# eib-128.net
KiCad netlist of a schematic drawn in EAGLE
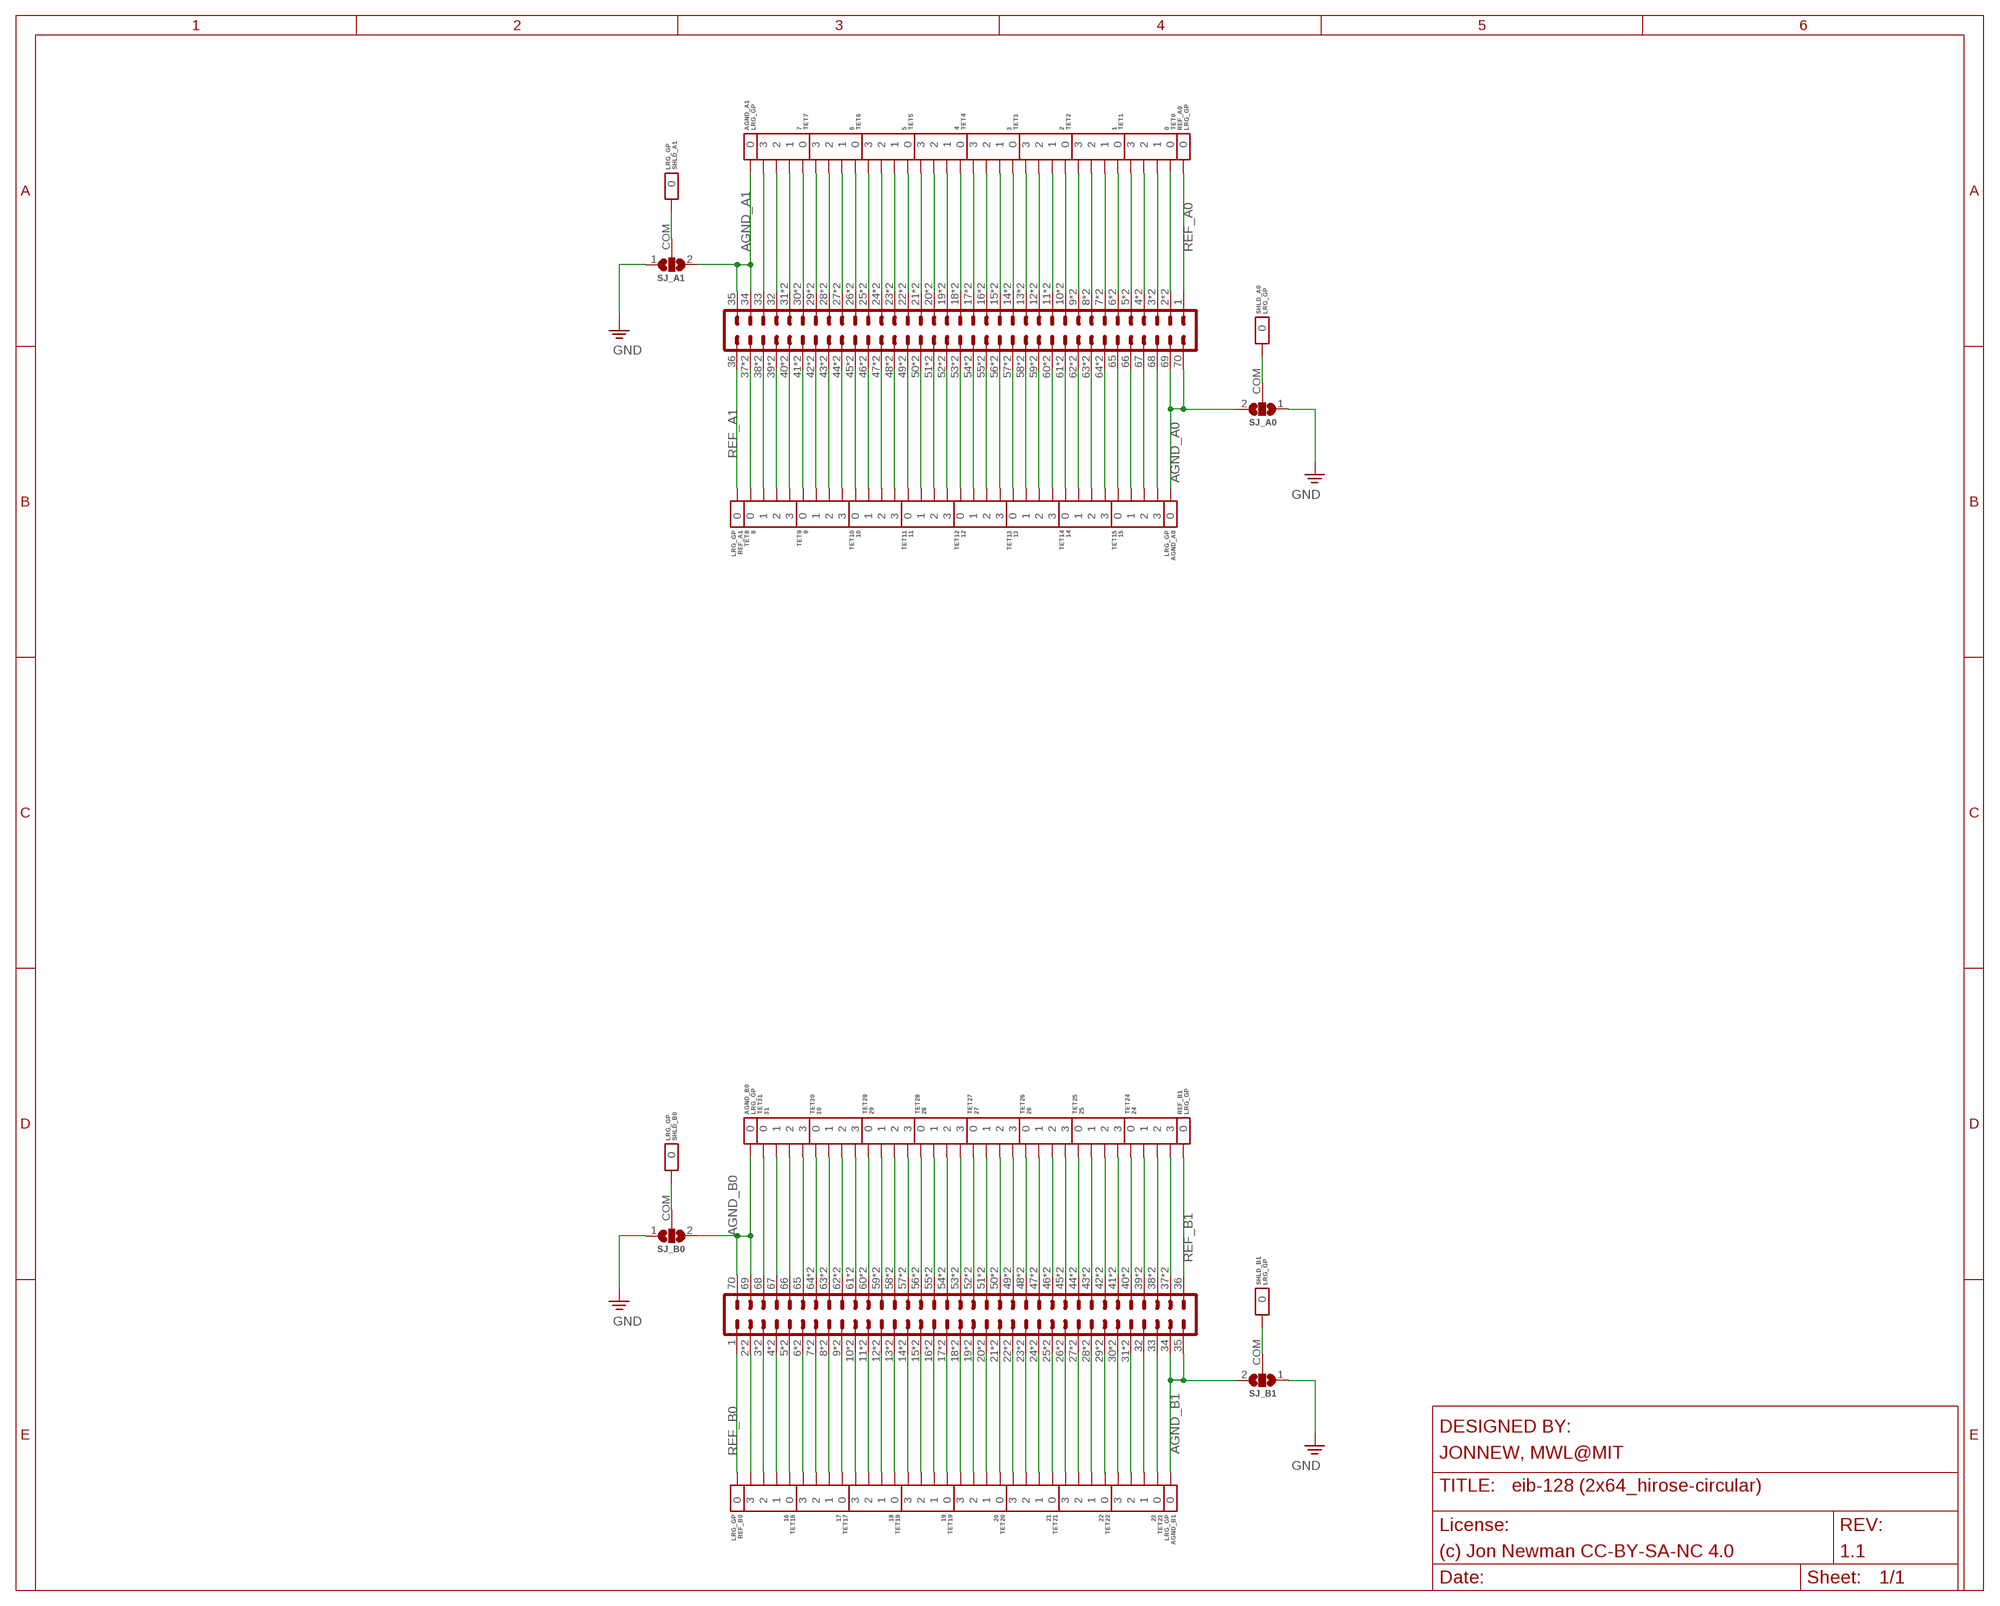
[diagram p0: schematic, sheet 1]

(export (version "E")
  (design (tool "Eeschema 10.0.6"))
  (components
    (comp (ref "AGND_A0")
      (value "LRG_GP")
      (footprint "eagle-import:GOLDPIN_0.5ID_0.7OD")
      (libsource (lib "eagle-import") (part "GOLDPIN_0.5ID_0.7OD"))
    )
    (comp (ref "AGND_A1")
      (value "LRG_GP")
      (footprint "eagle-import:GOLDPIN_0.5ID_0.7OD")
      (libsource (lib "eagle-import") (part "GOLDPIN_0.5ID_0.7OD"))
    )
    (comp (ref "AGND_B0")
      (value "LRG_GP")
      (footprint "eagle-import:GOLDPIN_0.5ID_0.7OD")
      (libsource (lib "eagle-import") (part "GOLDPIN_0.5ID_0.7OD"))
    )
    (comp (ref "AGND_B1")
      (value "LRG_GP")
      (footprint "eagle-import:GOLDPIN_0.5ID_0.7OD")
      (libsource (lib "eagle-import") (part "GOLDPIN_0.5ID_0.7OD"))
    )
    (comp (ref "AIN_N0T")
      (value "DF40HEAD")
      (footprint "eagle-import:DF40-70HEAD-EIB")
      (libsource (lib "eagle-import") (part "PINHD-2X35_DF40HEAD-EIB"))
    )
    (comp (ref "AIN_S0T")
      (value "DF40HEAD")
      (footprint "eagle-import:DF40-70HEAD-EIB")
      (libsource (lib "eagle-import") (part "PINHD-2X35_DF40HEAD-EIB"))
    )
    (comp (ref "REF_A0")
      (value "LRG_GP")
      (footprint "eagle-import:GOLDPIN_0.5ID_0.7OD")
      (libsource (lib "eagle-import") (part "GOLDPIN_0.5ID_0.7OD"))
    )
    (comp (ref "REF_A1")
      (value "LRG_GP")
      (footprint "eagle-import:GOLDPIN_0.5ID_0.7OD")
      (libsource (lib "eagle-import") (part "GOLDPIN_0.5ID_0.7OD"))
    )
    (comp (ref "REF_B0")
      (value "LRG_GP")
      (footprint "eagle-import:GOLDPIN_0.5ID_0.7OD")
      (libsource (lib "eagle-import") (part "GOLDPIN_0.5ID_0.7OD"))
    )
    (comp (ref "REF_B1")
      (value "LRG_GP")
      (footprint "eagle-import:GOLDPIN_0.5ID_0.7OD")
      (libsource (lib "eagle-import") (part "GOLDPIN_0.5ID_0.7OD"))
    )
    (comp (ref "SHLD_A0")
      (value "LRG_GP")
      (footprint "eagle-import:GOLDPIN_0.5ID_0.7OD")
      (libsource (lib "eagle-import") (part "GOLDPIN_0.5ID_0.7OD"))
    )
    (comp (ref "SHLD_A1")
      (value "LRG_GP")
      (footprint "eagle-import:GOLDPIN_0.5ID_0.7OD")
      (libsource (lib "eagle-import") (part "GOLDPIN_0.5ID_0.7OD"))
    )
    (comp (ref "SHLD_B0")
      (value "LRG_GP")
      (footprint "eagle-import:GOLDPIN_0.5ID_0.7OD")
      (libsource (lib "eagle-import") (part "GOLDPIN_0.5ID_0.7OD"))
    )
    (comp (ref "SHLD_B1")
      (value "LRG_GP")
      (footprint "eagle-import:GOLDPIN_0.5ID_0.7OD")
      (libsource (lib "eagle-import") (part "GOLDPIN_0.5ID_0.7OD"))
    )
    (comp (ref "SJ_A0")
      (value "SJ2_0402")
      (footprint "eagle-import:SJ_2_0402")
      (libsource (lib "eagle-import") (part "SJ2_0402"))
    )
    (comp (ref "SJ_A1")
      (value "SJ2_0402")
      (footprint "eagle-import:SJ_2_0402")
      (libsource (lib "eagle-import") (part "SJ2_0402"))
    )
    (comp (ref "SJ_B0")
      (value "SJ2_0402")
      (footprint "eagle-import:SJ_2_0402")
      (libsource (lib "eagle-import") (part "SJ2_0402"))
    )
    (comp (ref "SJ_B1")
      (value "SJ2_0402")
      (footprint "eagle-import:SJ_2_0402")
      (libsource (lib "eagle-import") (part "SJ2_0402"))
    )
    (comp (ref "TET0")
      (value "0")
      (footprint "eagle-import:TETRODE_128_0.5ID_0.7OD")
      (libsource (lib "eagle-import") (part "TETRODE_128_0.5ID_0.7OD"))
    )
    (comp (ref "TET1")
      (value "1")
      (footprint "eagle-import:TETRODE_128_0.5ID_0.7OD")
      (libsource (lib "eagle-import") (part "TETRODE_128_0.5ID_0.7OD"))
    )
    (comp (ref "TET2")
      (value "2")
      (footprint "eagle-import:TETRODE_128_0.5ID_0.7OD")
      (libsource (lib "eagle-import") (part "TETRODE_128_0.5ID_0.7OD"))
    )
    (comp (ref "TET3")
      (value "3")
      (footprint "eagle-import:TETRODE_128_0.5ID_0.7OD")
      (libsource (lib "eagle-import") (part "TETRODE_128_0.5ID_0.7OD"))
    )
    (comp (ref "TET4")
      (value "4")
      (footprint "eagle-import:TETRODE_128_0.5ID_0.7OD")
      (libsource (lib "eagle-import") (part "TETRODE_128_0.5ID_0.7OD"))
    )
    (comp (ref "TET5")
      (value "5")
      (footprint "eagle-import:TETRODE_128_0.5ID_0.7OD")
      (libsource (lib "eagle-import") (part "TETRODE_128_0.5ID_0.7OD"))
    )
    (comp (ref "TET6")
      (value "6")
      (footprint "eagle-import:TETRODE_128_0.5ID_0.7OD")
      (libsource (lib "eagle-import") (part "TETRODE_128_0.5ID_0.7OD"))
    )
    (comp (ref "TET7")
      (value "7")
      (footprint "eagle-import:TETRODE_128_0.5ID_0.7OD")
      (libsource (lib "eagle-import") (part "TETRODE_128_0.5ID_0.7OD"))
    )
    (comp (ref "TET8")
      (value "8")
      (footprint "eagle-import:TETRODE_128_0.5ID_0.7OD")
      (libsource (lib "eagle-import") (part "TETRODE_128_0.5ID_0.7OD"))
    )
    (comp (ref "TET9")
      (value "9")
      (footprint "eagle-import:TETRODE_128_0.5ID_0.7OD")
      (libsource (lib "eagle-import") (part "TETRODE_128_0.5ID_0.7OD"))
    )
    (comp (ref "TET10")
      (value "10")
      (footprint "eagle-import:TETRODE_128_0.5ID_0.7OD")
      (libsource (lib "eagle-import") (part "TETRODE_128_0.5ID_0.7OD"))
    )
    (comp (ref "TET11")
      (value "11")
      (footprint "eagle-import:TETRODE_128_0.5ID_0.7OD")
      (libsource (lib "eagle-import") (part "TETRODE_128_0.5ID_0.7OD"))
    )
    (comp (ref "TET12")
      (value "12")
      (footprint "eagle-import:TETRODE_128_0.5ID_0.7OD")
      (libsource (lib "eagle-import") (part "TETRODE_128_0.5ID_0.7OD"))
    )
    (comp (ref "TET13")
      (value "13")
      (footprint "eagle-import:TETRODE_128_0.5ID_0.7OD")
      (libsource (lib "eagle-import") (part "TETRODE_128_0.5ID_0.7OD"))
    )
    (comp (ref "TET14")
      (value "14")
      (footprint "eagle-import:TETRODE_128_0.5ID_0.7OD")
      (libsource (lib "eagle-import") (part "TETRODE_128_0.5ID_0.7OD"))
    )
    (comp (ref "TET15")
      (value "15")
      (footprint "eagle-import:TETRODE_128_0.5ID_0.7OD")
      (libsource (lib "eagle-import") (part "TETRODE_128_0.5ID_0.7OD"))
    )
    (comp (ref "TET16")
      (value "16")
      (footprint "eagle-import:TETRODE_128_0.5ID_0.7OD")
      (libsource (lib "eagle-import") (part "TETRODE_128_0.5ID_0.7OD"))
    )
    (comp (ref "TET17")
      (value "17")
      (footprint "eagle-import:TETRODE_128_0.5ID_0.7OD")
      (libsource (lib "eagle-import") (part "TETRODE_128_0.5ID_0.7OD"))
    )
    (comp (ref "TET18")
      (value "18")
      (footprint "eagle-import:TETRODE_128_0.5ID_0.7OD")
      (libsource (lib "eagle-import") (part "TETRODE_128_0.5ID_0.7OD"))
    )
    (comp (ref "TET19")
      (value "19")
      (footprint "eagle-import:TETRODE_128_0.5ID_0.7OD")
      (libsource (lib "eagle-import") (part "TETRODE_128_0.5ID_0.7OD"))
    )
    (comp (ref "TET20")
      (value "20")
      (footprint "eagle-import:TETRODE_128_0.5ID_0.7OD")
      (libsource (lib "eagle-import") (part "TETRODE_128_0.5ID_0.7OD"))
    )
    (comp (ref "TET21")
      (value "21")
      (footprint "eagle-import:TETRODE_128_0.5ID_0.7OD")
      (libsource (lib "eagle-import") (part "TETRODE_128_0.5ID_0.7OD"))
    )
    (comp (ref "TET22")
      (value "22")
      (footprint "eagle-import:TETRODE_128_0.5ID_0.7OD")
      (libsource (lib "eagle-import") (part "TETRODE_128_0.5ID_0.7OD"))
    )
    (comp (ref "TET23")
      (value "23")
      (footprint "eagle-import:TETRODE_128_0.5ID_0.7OD")
      (libsource (lib "eagle-import") (part "TETRODE_128_0.5ID_0.7OD"))
    )
    (comp (ref "TET24")
      (value "24")
      (footprint "eagle-import:TETRODE_128_0.5ID_0.7OD")
      (libsource (lib "eagle-import") (part "TETRODE_128_0.5ID_0.7OD"))
    )
    (comp (ref "TET25")
      (value "25")
      (footprint "eagle-import:TETRODE_128_0.5ID_0.7OD")
      (libsource (lib "eagle-import") (part "TETRODE_128_0.5ID_0.7OD"))
    )
    (comp (ref "TET26")
      (value "26")
      (footprint "eagle-import:TETRODE_128_0.5ID_0.7OD")
      (libsource (lib "eagle-import") (part "TETRODE_128_0.5ID_0.7OD"))
    )
    (comp (ref "TET27")
      (value "27")
      (footprint "eagle-import:TETRODE_128_0.5ID_0.7OD")
      (libsource (lib "eagle-import") (part "TETRODE_128_0.5ID_0.7OD"))
    )
    (comp (ref "TET28")
      (value "28")
      (footprint "eagle-import:TETRODE_128_0.5ID_0.7OD")
      (libsource (lib "eagle-import") (part "TETRODE_128_0.5ID_0.7OD"))
    )
    (comp (ref "TET29")
      (value "29")
      (footprint "eagle-import:TETRODE_128_0.5ID_0.7OD")
      (libsource (lib "eagle-import") (part "TETRODE_128_0.5ID_0.7OD"))
    )
    (comp (ref "TET30")
      (value "30")
      (footprint "eagle-import:TETRODE_128_0.5ID_0.7OD")
      (libsource (lib "eagle-import") (part "TETRODE_128_0.5ID_0.7OD"))
    )
    (comp (ref "TET31")
      (value "31")
      (footprint "eagle-import:TETRODE_128_0.5ID_0.7OD")
      (libsource (lib "eagle-import") (part "TETRODE_128_0.5ID_0.7OD"))
    )
  )
  (nets
    (net (code "1") (name "/AGND_A0") (class "Default")
      (node (ref "AGND_A0") (pin "P$1") (pinfunction "0_P$1") (pintype "bidirectional"))
      (node (ref "AIN_N0T") (pin "69") (pinfunction "69_69") (pintype "bidirectional"))
      (node (ref "AIN_N0T") (pin "70") (pinfunction "70_70") (pintype "bidirectional"))
      (node (ref "SJ_A0") (pin "2") (pinfunction "2_2") (pintype "passive"))
    )
    (net (code "2") (name "/AGND_A1") (class "Default")
      (node (ref "AGND_A1") (pin "P$1") (pinfunction "0_P$1") (pintype "bidirectional"))
      (node (ref "AIN_N0T") (pin "34") (pinfunction "34_34") (pintype "bidirectional"))
      (node (ref "AIN_N0T") (pin "35") (pinfunction "35_35") (pintype "bidirectional"))
      (node (ref "SJ_A1") (pin "2") (pinfunction "2_2") (pintype "passive"))
    )
    (net (code "3") (name "/AGND_B0") (class "Default")
      (node (ref "AGND_B0") (pin "P$1") (pinfunction "0_P$1") (pintype "bidirectional"))
      (node (ref "AIN_S0T") (pin "69") (pinfunction "69_69") (pintype "bidirectional"))
      (node (ref "AIN_S0T") (pin "70") (pinfunction "70_70") (pintype "bidirectional"))
      (node (ref "SJ_B0") (pin "2") (pinfunction "2_2") (pintype "passive"))
    )
    (net (code "4") (name "/AGND_B1") (class "Default")
      (node (ref "AGND_B1") (pin "P$1") (pinfunction "0_P$1") (pintype "bidirectional"))
      (node (ref "AIN_S0T") (pin "34") (pinfunction "34_34") (pintype "bidirectional"))
      (node (ref "AIN_S0T") (pin "35") (pinfunction "35_35") (pintype "bidirectional"))
      (node (ref "SJ_B1") (pin "2") (pinfunction "2_2") (pintype "passive"))
    )
    (net (code "5") (name "/REF_A0") (class "Default")
      (node (ref "AIN_N0T") (pin "1") (pinfunction "1_1") (pintype "bidirectional"))
      (node (ref "REF_A0") (pin "P$1") (pinfunction "0_P$1") (pintype "bidirectional"))
    )
    (net (code "6") (name "/REF_A1") (class "Default")
      (node (ref "AIN_N0T") (pin "36") (pinfunction "36_36") (pintype "bidirectional"))
      (node (ref "REF_A1") (pin "P$1") (pinfunction "0_P$1") (pintype "bidirectional"))
    )
    (net (code "7") (name "/REF_B0") (class "Default")
      (node (ref "AIN_S0T") (pin "1") (pinfunction "1_1") (pintype "bidirectional"))
      (node (ref "REF_B0") (pin "P$1") (pinfunction "0_P$1") (pintype "bidirectional"))
    )
    (net (code "8") (name "/REF_B1") (class "Default")
      (node (ref "AIN_S0T") (pin "36") (pinfunction "36_36") (pintype "bidirectional"))
      (node (ref "REF_B1") (pin "P$1") (pinfunction "0_P$1") (pintype "bidirectional"))
    )
    (net (code "9") (name "GND") (class "Default")
      (node (ref "SJ_A0") (pin "1") (pinfunction "1_1") (pintype "passive"))
      (node (ref "SJ_A1") (pin "1") (pinfunction "1_1") (pintype "passive"))
      (node (ref "SJ_B0") (pin "1") (pinfunction "1_1") (pintype "passive"))
      (node (ref "SJ_B1") (pin "1") (pinfunction "1_1") (pintype "passive"))
    )
    (net (code "10") (name "Net-(AIN_N0T-2-PadP2)") (class "Default")
      (node (ref "AIN_N0T") (pin "2") (pinfunction "2_2") (pintype "bidirectional"))
      (node (ref "AIN_N0T") (pin "P2") (pinfunction "2_P2") (pintype "bidirectional"))
      (node (ref "TET0") (pin "0") (pinfunction "0_0") (pintype "bidirectional"))
    )
    (net (code "11") (name "Net-(AIN_N0T-3-PadP3)") (class "Default")
      (node (ref "AIN_N0T") (pin "3") (pinfunction "3_3") (pintype "bidirectional"))
      (node (ref "AIN_N0T") (pin "P3") (pinfunction "3_P3") (pintype "bidirectional"))
      (node (ref "TET0") (pin "1") (pinfunction "1_1") (pintype "bidirectional"))
    )
    (net (code "12") (name "Net-(AIN_N0T-4-PadP4)") (class "Default")
      (node (ref "AIN_N0T") (pin "4") (pinfunction "4_4") (pintype "bidirectional"))
      (node (ref "AIN_N0T") (pin "P4") (pinfunction "4_P4") (pintype "bidirectional"))
      (node (ref "TET0") (pin "2") (pinfunction "2_2") (pintype "bidirectional"))
    )
    (net (code "13") (name "Net-(AIN_N0T-5-PadP5)") (class "Default")
      (node (ref "AIN_N0T") (pin "5") (pinfunction "5_5") (pintype "bidirectional"))
      (node (ref "AIN_N0T") (pin "P5") (pinfunction "5_P5") (pintype "bidirectional"))
      (node (ref "TET0") (pin "3") (pinfunction "3_3") (pintype "bidirectional"))
    )
    (net (code "14") (name "Net-(AIN_N0T-6-PadP6)") (class "Default")
      (node (ref "AIN_N0T") (pin "6") (pinfunction "6_6") (pintype "bidirectional"))
      (node (ref "AIN_N0T") (pin "P6") (pinfunction "6_P6") (pintype "bidirectional"))
      (node (ref "TET1") (pin "0") (pinfunction "0_0") (pintype "bidirectional"))
    )
    (net (code "15") (name "Net-(AIN_N0T-7-PadP7)") (class "Default")
      (node (ref "AIN_N0T") (pin "7") (pinfunction "7_7") (pintype "bidirectional"))
      (node (ref "AIN_N0T") (pin "P7") (pinfunction "7_P7") (pintype "bidirectional"))
      (node (ref "TET1") (pin "1") (pinfunction "1_1") (pintype "bidirectional"))
    )
    (net (code "16") (name "Net-(AIN_N0T-8-PadP8)") (class "Default")
      (node (ref "AIN_N0T") (pin "8") (pinfunction "8_8") (pintype "bidirectional"))
      (node (ref "AIN_N0T") (pin "P8") (pinfunction "8_P8") (pintype "bidirectional"))
      (node (ref "TET1") (pin "2") (pinfunction "2_2") (pintype "bidirectional"))
    )
    (net (code "17") (name "Net-(AIN_N0T-9-PadP9)") (class "Default")
      (node (ref "AIN_N0T") (pin "9") (pinfunction "9_9") (pintype "bidirectional"))
      (node (ref "AIN_N0T") (pin "P9") (pinfunction "9_P9") (pintype "bidirectional"))
      (node (ref "TET1") (pin "3") (pinfunction "3_3") (pintype "bidirectional"))
    )
    (net (code "18") (name "Net-(AIN_N0T-10-PadP10)") (class "Default")
      (node (ref "AIN_N0T") (pin "10") (pinfunction "10_10") (pintype "bidirectional"))
      (node (ref "AIN_N0T") (pin "P10") (pinfunction "10_P10") (pintype "bidirectional"))
      (node (ref "TET2") (pin "0") (pinfunction "0_0") (pintype "bidirectional"))
    )
    (net (code "19") (name "Net-(AIN_N0T-11-PadP11)") (class "Default")
      (node (ref "AIN_N0T") (pin "11") (pinfunction "11_11") (pintype "bidirectional"))
      (node (ref "AIN_N0T") (pin "P11") (pinfunction "11_P11") (pintype "bidirectional"))
      (node (ref "TET2") (pin "1") (pinfunction "1_1") (pintype "bidirectional"))
    )
    (net (code "20") (name "Net-(AIN_N0T-12-PadP12)") (class "Default")
      (node (ref "AIN_N0T") (pin "12") (pinfunction "12_12") (pintype "bidirectional"))
      (node (ref "AIN_N0T") (pin "P12") (pinfunction "12_P12") (pintype "bidirectional"))
      (node (ref "TET2") (pin "2") (pinfunction "2_2") (pintype "bidirectional"))
    )
    (net (code "21") (name "Net-(AIN_N0T-13-PadP13)") (class "Default")
      (node (ref "AIN_N0T") (pin "13") (pinfunction "13_13") (pintype "bidirectional"))
      (node (ref "AIN_N0T") (pin "P13") (pinfunction "13_P13") (pintype "bidirectional"))
      (node (ref "TET2") (pin "3") (pinfunction "3_3") (pintype "bidirectional"))
    )
    (net (code "22") (name "Net-(AIN_N0T-14-PadP14)") (class "Default")
      (node (ref "AIN_N0T") (pin "14") (pinfunction "14_14") (pintype "bidirectional"))
      (node (ref "AIN_N0T") (pin "P14") (pinfunction "14_P14") (pintype "bidirectional"))
      (node (ref "TET3") (pin "0") (pinfunction "0_0") (pintype "bidirectional"))
    )
    (net (code "23") (name "Net-(AIN_N0T-15-PadP15)") (class "Default")
      (node (ref "AIN_N0T") (pin "15") (pinfunction "15_15") (pintype "bidirectional"))
      (node (ref "AIN_N0T") (pin "P15") (pinfunction "15_P15") (pintype "bidirectional"))
      (node (ref "TET3") (pin "1") (pinfunction "1_1") (pintype "bidirectional"))
    )
    (net (code "24") (name "Net-(AIN_N0T-16-PadP16)") (class "Default")
      (node (ref "AIN_N0T") (pin "16") (pinfunction "16_16") (pintype "bidirectional"))
      (node (ref "AIN_N0T") (pin "P16") (pinfunction "16_P16") (pintype "bidirectional"))
      (node (ref "TET3") (pin "2") (pinfunction "2_2") (pintype "bidirectional"))
    )
    (net (code "25") (name "Net-(AIN_N0T-17-PadP17)") (class "Default")
      (node (ref "AIN_N0T") (pin "17") (pinfunction "17_17") (pintype "bidirectional"))
      (node (ref "AIN_N0T") (pin "P17") (pinfunction "17_P17") (pintype "bidirectional"))
      (node (ref "TET3") (pin "3") (pinfunction "3_3") (pintype "bidirectional"))
    )
    (net (code "26") (name "Net-(AIN_N0T-18-PadP18)") (class "Default")
      (node (ref "AIN_N0T") (pin "18") (pinfunction "18_18") (pintype "bidirectional"))
      (node (ref "AIN_N0T") (pin "P18") (pinfunction "18_P18") (pintype "bidirectional"))
      (node (ref "TET4") (pin "0") (pinfunction "0_0") (pintype "bidirectional"))
    )
    (net (code "27") (name "Net-(AIN_N0T-19-PadP19)") (class "Default")
      (node (ref "AIN_N0T") (pin "19") (pinfunction "19_19") (pintype "bidirectional"))
      (node (ref "AIN_N0T") (pin "P19") (pinfunction "19_P19") (pintype "bidirectional"))
      (node (ref "TET4") (pin "1") (pinfunction "1_1") (pintype "bidirectional"))
    )
    (net (code "28") (name "Net-(AIN_N0T-20-PadP20)") (class "Default")
      (node (ref "AIN_N0T") (pin "20") (pinfunction "20_20") (pintype "bidirectional"))
      (node (ref "AIN_N0T") (pin "P20") (pinfunction "20_P20") (pintype "bidirectional"))
      (node (ref "TET4") (pin "2") (pinfunction "2_2") (pintype "bidirectional"))
    )
    (net (code "29") (name "Net-(AIN_N0T-21-PadP21)") (class "Default")
      (node (ref "AIN_N0T") (pin "21") (pinfunction "21_21") (pintype "bidirectional"))
      (node (ref "AIN_N0T") (pin "P21") (pinfunction "21_P21") (pintype "bidirectional"))
      (node (ref "TET4") (pin "3") (pinfunction "3_3") (pintype "bidirectional"))
    )
    (net (code "30") (name "Net-(AIN_N0T-22-PadP22)") (class "Default")
      (node (ref "AIN_N0T") (pin "22") (pinfunction "22_22") (pintype "bidirectional"))
      (node (ref "AIN_N0T") (pin "P22") (pinfunction "22_P22") (pintype "bidirectional"))
      (node (ref "TET5") (pin "0") (pinfunction "0_0") (pintype "bidirectional"))
    )
    (net (code "31") (name "Net-(AIN_N0T-23-PadP23)") (class "Default")
      (node (ref "AIN_N0T") (pin "23") (pinfunction "23_23") (pintype "bidirectional"))
      (node (ref "AIN_N0T") (pin "P23") (pinfunction "23_P23") (pintype "bidirectional"))
      (node (ref "TET5") (pin "1") (pinfunction "1_1") (pintype "bidirectional"))
    )
    (net (code "32") (name "Net-(AIN_N0T-24-PadP24)") (class "Default")
      (node (ref "AIN_N0T") (pin "24") (pinfunction "24_24") (pintype "bidirectional"))
      (node (ref "AIN_N0T") (pin "P24") (pinfunction "24_P24") (pintype "bidirectional"))
      (node (ref "TET5") (pin "2") (pinfunction "2_2") (pintype "bidirectional"))
    )
    (net (code "33") (name "Net-(AIN_N0T-25-PadP25)") (class "Default")
      (node (ref "AIN_N0T") (pin "25") (pinfunction "25_25") (pintype "bidirectional"))
      (node (ref "AIN_N0T") (pin "P25") (pinfunction "25_P25") (pintype "bidirectional"))
      (node (ref "TET5") (pin "3") (pinfunction "3_3") (pintype "bidirectional"))
    )
    (net (code "34") (name "Net-(AIN_N0T-26-PadP26)") (class "Default")
      (node (ref "AIN_N0T") (pin "26") (pinfunction "26_26") (pintype "bidirectional"))
      (node (ref "AIN_N0T") (pin "P26") (pinfunction "26_P26") (pintype "bidirectional"))
      (node (ref "TET6") (pin "0") (pinfunction "0_0") (pintype "bidirectional"))
    )
    (net (code "35") (name "Net-(AIN_N0T-27-PadP27)") (class "Default")
      (node (ref "AIN_N0T") (pin "27") (pinfunction "27_27") (pintype "bidirectional"))
      (node (ref "AIN_N0T") (pin "P27") (pinfunction "27_P27") (pintype "bidirectional"))
      (node (ref "TET6") (pin "1") (pinfunction "1_1") (pintype "bidirectional"))
    )
    (net (code "36") (name "Net-(AIN_N0T-28-PadP28)") (class "Default")
      (node (ref "AIN_N0T") (pin "28") (pinfunction "28_28") (pintype "bidirectional"))
      (node (ref "AIN_N0T") (pin "P28") (pinfunction "28_P28") (pintype "bidirectional"))
      (node (ref "TET6") (pin "2") (pinfunction "2_2") (pintype "bidirectional"))
    )
    (net (code "37") (name "Net-(AIN_N0T-29-PadP29)") (class "Default")
      (node (ref "AIN_N0T") (pin "29") (pinfunction "29_29") (pintype "bidirectional"))
      (node (ref "AIN_N0T") (pin "P29") (pinfunction "29_P29") (pintype "bidirectional"))
      (node (ref "TET6") (pin "3") (pinfunction "3_3") (pintype "bidirectional"))
    )
    (net (code "38") (name "Net-(AIN_N0T-30-PadP30)") (class "Default")
      (node (ref "AIN_N0T") (pin "30") (pinfunction "30_30") (pintype "bidirectional"))
      (node (ref "AIN_N0T") (pin "P30") (pinfunction "30_P30") (pintype "bidirectional"))
      (node (ref "TET7") (pin "0") (pinfunction "0_0") (pintype "bidirectional"))
    )
    (net (code "39") (name "Net-(AIN_N0T-31-PadP31)") (class "Default")
      (node (ref "AIN_N0T") (pin "31") (pinfunction "31_31") (pintype "bidirectional"))
      (node (ref "AIN_N0T") (pin "P31") (pinfunction "31_P31") (pintype "bidirectional"))
      (node (ref "TET7") (pin "1") (pinfunction "1_1") (pintype "bidirectional"))
    )
    (net (code "40") (name "Net-(AIN_N0T-37-PadP37)") (class "Default")
      (node (ref "AIN_N0T") (pin "37") (pinfunction "37_37") (pintype "bidirectional"))
      (node (ref "AIN_N0T") (pin "P37") (pinfunction "37_P37") (pintype "bidirectional"))
      (node (ref "TET8") (pin "0") (pinfunction "0_0") (pintype "bidirectional"))
    )
    (net (code "41") (name "Net-(AIN_N0T-38-PadP38)") (class "Default")
      (node (ref "AIN_N0T") (pin "38") (pinfunction "38_38") (pintype "bidirectional"))
      (node (ref "AIN_N0T") (pin "P38") (pinfunction "38_P38") (pintype "bidirectional"))
      (node (ref "TET8") (pin "1") (pinfunction "1_1") (pintype "bidirectional"))
    )
    (net (code "42") (name "Net-(AIN_N0T-39-PadP39)") (class "Default")
      (node (ref "AIN_N0T") (pin "39") (pinfunction "39_39") (pintype "bidirectional"))
      (node (ref "AIN_N0T") (pin "P39") (pinfunction "39_P39") (pintype "bidirectional"))
      (node (ref "TET8") (pin "2") (pinfunction "2_2") (pintype "bidirectional"))
    )
    (net (code "43") (name "Net-(AIN_N0T-40-PadP40)") (class "Default")
      (node (ref "AIN_N0T") (pin "40") (pinfunction "40_40") (pintype "bidirectional"))
      (node (ref "AIN_N0T") (pin "P40") (pinfunction "40_P40") (pintype "bidirectional"))
      (node (ref "TET8") (pin "3") (pinfunction "3_3") (pintype "bidirectional"))
    )
    (net (code "44") (name "Net-(AIN_N0T-41-PadP41)") (class "Default")
      (node (ref "AIN_N0T") (pin "41") (pinfunction "41_41") (pintype "bidirectional"))
      (node (ref "AIN_N0T") (pin "P41") (pinfunction "41_P41") (pintype "bidirectional"))
      (node (ref "TET9") (pin "0") (pinfunction "0_0") (pintype "bidirectional"))
    )
    (net (code "45") (name "Net-(AIN_N0T-42-PadP42)") (class "Default")
      (node (ref "AIN_N0T") (pin "42") (pinfunction "42_42") (pintype "bidirectional"))
      (node (ref "AIN_N0T") (pin "P42") (pinfunction "42_P42") (pintype "bidirectional"))
      (node (ref "TET9") (pin "1") (pinfunction "1_1") (pintype "bidirectional"))
    )
    (net (code "46") (name "Net-(AIN_N0T-43-PadP43)") (class "Default")
      (node (ref "AIN_N0T") (pin "43") (pinfunction "43_43") (pintype "bidirectional"))
      (node (ref "AIN_N0T") (pin "P43") (pinfunction "43_P43") (pintype "bidirectional"))
      (node (ref "TET9") (pin "2") (pinfunction "2_2") (pintype "bidirectional"))
    )
    (net (code "47") (name "Net-(AIN_N0T-44-PadP44)") (class "Default")
      (node (ref "AIN_N0T") (pin "44") (pinfunction "44_44") (pintype "bidirectional"))
      (node (ref "AIN_N0T") (pin "P44") (pinfunction "44_P44") (pintype "bidirectional"))
      (node (ref "TET9") (pin "3") (pinfunction "3_3") (pintype "bidirectional"))
    )
    (net (code "48") (name "Net-(AIN_N0T-45-PadP45)") (class "Default")
      (node (ref "AIN_N0T") (pin "45") (pinfunction "45_45") (pintype "bidirectional"))
      (node (ref "AIN_N0T") (pin "P45") (pinfunction "45_P45") (pintype "bidirectional"))
      (node (ref "TET10") (pin "0") (pinfunction "0_0") (pintype "bidirectional"))
    )
    (net (code "49") (name "Net-(AIN_N0T-46-PadP46)") (class "Default")
      (node (ref "AIN_N0T") (pin "46") (pinfunction "46_46") (pintype "bidirectional"))
      (node (ref "AIN_N0T") (pin "P46") (pinfunction "46_P46") (pintype "bidirectional"))
      (node (ref "TET10") (pin "1") (pinfunction "1_1") (pintype "bidirectional"))
    )
    (net (code "50") (name "Net-(AIN_N0T-47-PadP47)") (class "Default")
      (node (ref "AIN_N0T") (pin "47") (pinfunction "47_47") (pintype "bidirectional"))
      (node (ref "AIN_N0T") (pin "P47") (pinfunction "47_P47") (pintype "bidirectional"))
      (node (ref "TET10") (pin "2") (pinfunction "2_2") (pintype "bidirectional"))
    )
    (net (code "51") (name "Net-(AIN_N0T-48-PadP48)") (class "Default")
      (node (ref "AIN_N0T") (pin "48") (pinfunction "48_48") (pintype "bidirectional"))
      (node (ref "AIN_N0T") (pin "P48") (pinfunction "48_P48") (pintype "bidirectional"))
      (node (ref "TET10") (pin "3") (pinfunction "3_3") (pintype "bidirectional"))
    )
    (net (code "52") (name "Net-(AIN_N0T-49-PadP49)") (class "Default")
      (node (ref "AIN_N0T") (pin "49") (pinfunction "49_49") (pintype "bidirectional"))
      (node (ref "AIN_N0T") (pin "P49") (pinfunction "49_P49") (pintype "bidirectional"))
      (node (ref "TET11") (pin "0") (pinfunction "0_0") (pintype "bidirectional"))
    )
    (net (code "53") (name "Net-(AIN_N0T-50-PadP50)") (class "Default")
      (node (ref "AIN_N0T") (pin "50") (pinfunction "50_50") (pintype "bidirectional"))
      (node (ref "AIN_N0T") (pin "P50") (pinfunction "50_P50") (pintype "bidirectional"))
      (node (ref "TET11") (pin "1") (pinfunction "1_1") (pintype "bidirectional"))
    )
    (net (code "54") (name "Net-(AIN_N0T-51-PadP51)") (class "Default")
      (node (ref "AIN_N0T") (pin "51") (pinfunction "51_51") (pintype "bidirectional"))
      (node (ref "AIN_N0T") (pin "P51") (pinfunction "51_P51") (pintype "bidirectional"))
      (node (ref "TET11") (pin "2") (pinfunction "2_2") (pintype "bidirectional"))
    )
    (net (code "55") (name "Net-(AIN_N0T-52-PadP52)") (class "Default")
      (node (ref "AIN_N0T") (pin "52") (pinfunction "52_52") (pintype "bidirectional"))
      (node (ref "AIN_N0T") (pin "P52") (pinfunction "52_P52") (pintype "bidirectional"))
      (node (ref "TET11") (pin "3") (pinfunction "3_3") (pintype "bidirectional"))
    )
    (net (code "56") (name "Net-(AIN_N0T-53-PadP53)") (class "Default")
      (node (ref "AIN_N0T") (pin "53") (pinfunction "53_53") (pintype "bidirectional"))
      (node (ref "AIN_N0T") (pin "P53") (pinfunction "53_P53") (pintype "bidirectional"))
      (node (ref "TET12") (pin "0") (pinfunction "0_0") (pintype "bidirectional"))
    )
    (net (code "57") (name "Net-(AIN_N0T-54-PadP54)") (class "Default")
      (node (ref "AIN_N0T") (pin "54") (pinfunction "54_54") (pintype "bidirectional"))
      (node (ref "AIN_N0T") (pin "P54") (pinfunction "54_P54") (pintype "bidirectional"))
      (node (ref "TET12") (pin "1") (pinfunction "1_1") (pintype "bidirectional"))
    )
    (net (code "58") (name "Net-(AIN_N0T-55-PadP55)") (class "Default")
      (node (ref "AIN_N0T") (pin "55") (pinfunction "55_55") (pintype "bidirectional"))
      (node (ref "AIN_N0T") (pin "P55") (pinfunction "55_P55") (pintype "bidirectional"))
      (node (ref "TET12") (pin "2") (pinfunction "2_2") (pintype "bidirectional"))
    )
    (net (code "59") (name "Net-(AIN_N0T-56-PadP56)") (class "Default")
      (node (ref "AIN_N0T") (pin "56") (pinfunction "56_56") (pintype "bidirectional"))
      (node (ref "AIN_N0T") (pin "P56") (pinfunction "56_P56") (pintype "bidirectional"))
      (node (ref "TET12") (pin "3") (pinfunction "3_3") (pintype "bidirectional"))
    )
    (net (code "60") (name "Net-(AIN_N0T-57-PadP57)") (class "Default")
      (node (ref "AIN_N0T") (pin "57") (pinfunction "57_57") (pintype "bidirectional"))
      (node (ref "AIN_N0T") (pin "P57") (pinfunction "57_P57") (pintype "bidirectional"))
      (node (ref "TET13") (pin "0") (pinfunction "0_0") (pintype "bidirectional"))
    )
    (net (code "61") (name "Net-(AIN_N0T-58-PadP58)") (class "Default")
      (node (ref "AIN_N0T") (pin "58") (pinfunction "58_58") (pintype "bidirectional"))
      (node (ref "AIN_N0T") (pin "P58") (pinfunction "58_P58") (pintype "bidirectional"))
      (node (ref "TET13") (pin "1") (pinfunction "1_1") (pintype "bidirectional"))
    )
    (net (code "62") (name "Net-(AIN_N0T-59-PadP59)") (class "Default")
      (node (ref "AIN_N0T") (pin "59") (pinfunction "59_59") (pintype "bidirectional"))
      (node (ref "AIN_N0T") (pin "P59") (pinfunction "59_P59") (pintype "bidirectional"))
      (node (ref "TET13") (pin "2") (pinfunction "2_2") (pintype "bidirectional"))
    )
    (net (code "63") (name "Net-(AIN_N0T-60-PadP60)") (class "Default")
      (node (ref "AIN_N0T") (pin "60") (pinfunction "60_60") (pintype "bidirectional"))
      (node (ref "AIN_N0T") (pin "P60") (pinfunction "60_P60") (pintype "bidirectional"))
      (node (ref "TET13") (pin "3") (pinfunction "3_3") (pintype "bidirectional"))
    )
    (net (code "64") (name "Net-(AIN_N0T-61-PadP61)") (class "Default")
      (node (ref "AIN_N0T") (pin "61") (pinfunction "61_61") (pintype "bidirectional"))
      (node (ref "AIN_N0T") (pin "P61") (pinfunction "61_P61") (pintype "bidirectional"))
      (node (ref "TET14") (pin "0") (pinfunction "0_0") (pintype "bidirectional"))
    )
    (net (code "65") (name "Net-(AIN_N0T-62-PadP62)") (class "Default")
      (node (ref "AIN_N0T") (pin "62") (pinfunction "62_62") (pintype "bidirectional"))
      (node (ref "AIN_N0T") (pin "P62") (pinfunction "62_P62") (pintype "bidirectional"))
      (node (ref "TET14") (pin "1") (pinfunction "1_1") (pintype "bidirectional"))
    )
    (net (code "66") (name "Net-(AIN_N0T-63-PadP63)") (class "Default")
      (node (ref "AIN_N0T") (pin "63") (pinfunction "63_63") (pintype "bidirectional"))
      (node (ref "AIN_N0T") (pin "P63") (pinfunction "63_P63") (pintype "bidirectional"))
      (node (ref "TET14") (pin "2") (pinfunction "2_2") (pintype "bidirectional"))
    )
    (net (code "67") (name "Net-(AIN_N0T-64-PadP64)") (class "Default")
      (node (ref "AIN_N0T") (pin "64") (pinfunction "64_64") (pintype "bidirectional"))
      (node (ref "AIN_N0T") (pin "P64") (pinfunction "64_P64") (pintype "bidirectional"))
      (node (ref "TET14") (pin "3") (pinfunction "3_3") (pintype "bidirectional"))
    )
    (net (code "68") (name "Net-(AIN_N0T-Pad32)") (class "Default")
      (node (ref "AIN_N0T") (pin "32") (pinfunction "32_32") (pintype "bidirectional"))
      (node (ref "TET7") (pin "2") (pinfunction "2_2") (pintype "bidirectional"))
    )
    (net (code "69") (name "Net-(AIN_N0T-Pad33)") (class "Default")
      (node (ref "AIN_N0T") (pin "33") (pinfunction "33_33") (pintype "bidirectional"))
      (node (ref "TET7") (pin "3") (pinfunction "3_3") (pintype "bidirectional"))
    )
    (net (code "70") (name "Net-(AIN_N0T-Pad65)") (class "Default")
      (node (ref "AIN_N0T") (pin "65") (pinfunction "65_65") (pintype "bidirectional"))
      (node (ref "TET15") (pin "0") (pinfunction "0_0") (pintype "bidirectional"))
    )
    (net (code "71") (name "Net-(AIN_N0T-Pad66)") (class "Default")
      (node (ref "AIN_N0T") (pin "66") (pinfunction "66_66") (pintype "bidirectional"))
      (node (ref "TET15") (pin "1") (pinfunction "1_1") (pintype "bidirectional"))
    )
    (net (code "72") (name "Net-(AIN_N0T-Pad67)") (class "Default")
      (node (ref "AIN_N0T") (pin "67") (pinfunction "67_67") (pintype "bidirectional"))
      (node (ref "TET15") (pin "2") (pinfunction "2_2") (pintype "bidirectional"))
    )
    (net (code "73") (name "Net-(AIN_N0T-Pad68)") (class "Default")
      (node (ref "AIN_N0T") (pin "68") (pinfunction "68_68") (pintype "bidirectional"))
      (node (ref "TET15") (pin "3") (pinfunction "3_3") (pintype "bidirectional"))
    )
    (net (code "74") (name "Net-(AIN_S0T-2-PadP2)") (class "Default")
      (node (ref "AIN_S0T") (pin "2") (pinfunction "2_2") (pintype "bidirectional"))
      (node (ref "AIN_S0T") (pin "P2") (pinfunction "2_P2") (pintype "bidirectional"))
      (node (ref "TET16") (pin "3") (pinfunction "3_3") (pintype "bidirectional"))
    )
    (net (code "75") (name "Net-(AIN_S0T-3-PadP3)") (class "Default")
      (node (ref "AIN_S0T") (pin "3") (pinfunction "3_3") (pintype "bidirectional"))
      (node (ref "AIN_S0T") (pin "P3") (pinfunction "3_P3") (pintype "bidirectional"))
      (node (ref "TET16") (pin "2") (pinfunction "2_2") (pintype "bidirectional"))
    )
    (net (code "76") (name "Net-(AIN_S0T-4-PadP4)") (class "Default")
      (node (ref "AIN_S0T") (pin "4") (pinfunction "4_4") (pintype "bidirectional"))
      (node (ref "AIN_S0T") (pin "P4") (pinfunction "4_P4") (pintype "bidirectional"))
      (node (ref "TET16") (pin "1") (pinfunction "1_1") (pintype "bidirectional"))
    )
    (net (code "77") (name "Net-(AIN_S0T-5-PadP5)") (class "Default")
      (node (ref "AIN_S0T") (pin "5") (pinfunction "5_5") (pintype "bidirectional"))
      (node (ref "AIN_S0T") (pin "P5") (pinfunction "5_P5") (pintype "bidirectional"))
      (node (ref "TET16") (pin "0") (pinfunction "0_0") (pintype "bidirectional"))
    )
    (net (code "78") (name "Net-(AIN_S0T-6-PadP6)") (class "Default")
      (node (ref "AIN_S0T") (pin "6") (pinfunction "6_6") (pintype "bidirectional"))
      (node (ref "AIN_S0T") (pin "P6") (pinfunction "6_P6") (pintype "bidirectional"))
      (node (ref "TET17") (pin "3") (pinfunction "3_3") (pintype "bidirectional"))
    )
    (net (code "79") (name "Net-(AIN_S0T-7-PadP7)") (class "Default")
      (node (ref "AIN_S0T") (pin "7") (pinfunction "7_7") (pintype "bidirectional"))
      (node (ref "AIN_S0T") (pin "P7") (pinfunction "7_P7") (pintype "bidirectional"))
      (node (ref "TET17") (pin "2") (pinfunction "2_2") (pintype "bidirectional"))
    )
    (net (code "80") (name "Net-(AIN_S0T-8-PadP8)") (class "Default")
      (node (ref "AIN_S0T") (pin "8") (pinfunction "8_8") (pintype "bidirectional"))
      (node (ref "AIN_S0T") (pin "P8") (pinfunction "8_P8") (pintype "bidirectional"))
      (node (ref "TET17") (pin "1") (pinfunction "1_1") (pintype "bidirectional"))
    )
    (net (code "81") (name "Net-(AIN_S0T-9-PadP9)") (class "Default")
      (node (ref "AIN_S0T") (pin "9") (pinfunction "9_9") (pintype "bidirectional"))
      (node (ref "AIN_S0T") (pin "P9") (pinfunction "9_P9") (pintype "bidirectional"))
      (node (ref "TET17") (pin "0") (pinfunction "0_0") (pintype "bidirectional"))
    )
    (net (code "82") (name "Net-(AIN_S0T-10-PadP10)") (class "Default")
      (node (ref "AIN_S0T") (pin "10") (pinfunction "10_10") (pintype "bidirectional"))
      (node (ref "AIN_S0T") (pin "P10") (pinfunction "10_P10") (pintype "bidirectional"))
      (node (ref "TET18") (pin "3") (pinfunction "3_3") (pintype "bidirectional"))
    )
    (net (code "83") (name "Net-(AIN_S0T-11-PadP11)") (class "Default")
      (node (ref "AIN_S0T") (pin "11") (pinfunction "11_11") (pintype "bidirectional"))
      (node (ref "AIN_S0T") (pin "P11") (pinfunction "11_P11") (pintype "bidirectional"))
      (node (ref "TET18") (pin "2") (pinfunction "2_2") (pintype "bidirectional"))
    )
    (net (code "84") (name "Net-(AIN_S0T-12-PadP12)") (class "Default")
      (node (ref "AIN_S0T") (pin "12") (pinfunction "12_12") (pintype "bidirectional"))
      (node (ref "AIN_S0T") (pin "P12") (pinfunction "12_P12") (pintype "bidirectional"))
      (node (ref "TET18") (pin "1") (pinfunction "1_1") (pintype "bidirectional"))
    )
    (net (code "85") (name "Net-(AIN_S0T-13-PadP13)") (class "Default")
      (node (ref "AIN_S0T") (pin "13") (pinfunction "13_13") (pintype "bidirectional"))
      (node (ref "AIN_S0T") (pin "P13") (pinfunction "13_P13") (pintype "bidirectional"))
      (node (ref "TET18") (pin "0") (pinfunction "0_0") (pintype "bidirectional"))
    )
    (net (code "86") (name "Net-(AIN_S0T-14-PadP14)") (class "Default")
      (node (ref "AIN_S0T") (pin "14") (pinfunction "14_14") (pintype "bidirectional"))
      (node (ref "AIN_S0T") (pin "P14") (pinfunction "14_P14") (pintype "bidirectional"))
      (node (ref "TET19") (pin "3") (pinfunction "3_3") (pintype "bidirectional"))
    )
    (net (code "87") (name "Net-(AIN_S0T-15-PadP15)") (class "Default")
      (node (ref "AIN_S0T") (pin "15") (pinfunction "15_15") (pintype "bidirectional"))
      (node (ref "AIN_S0T") (pin "P15") (pinfunction "15_P15") (pintype "bidirectional"))
      (node (ref "TET19") (pin "2") (pinfunction "2_2") (pintype "bidirectional"))
    )
    (net (code "88") (name "Net-(AIN_S0T-16-PadP16)") (class "Default")
      (node (ref "AIN_S0T") (pin "16") (pinfunction "16_16") (pintype "bidirectional"))
      (node (ref "AIN_S0T") (pin "P16") (pinfunction "16_P16") (pintype "bidirectional"))
      (node (ref "TET19") (pin "1") (pinfunction "1_1") (pintype "bidirectional"))
    )
    (net (code "89") (name "Net-(AIN_S0T-17-PadP17)") (class "Default")
      (node (ref "AIN_S0T") (pin "17") (pinfunction "17_17") (pintype "bidirectional"))
      (node (ref "AIN_S0T") (pin "P17") (pinfunction "17_P17") (pintype "bidirectional"))
      (node (ref "TET19") (pin "0") (pinfunction "0_0") (pintype "bidirectional"))
    )
    (net (code "90") (name "Net-(AIN_S0T-18-PadP18)") (class "Default")
      (node (ref "AIN_S0T") (pin "18") (pinfunction "18_18") (pintype "bidirectional"))
      (node (ref "AIN_S0T") (pin "P18") (pinfunction "18_P18") (pintype "bidirectional"))
      (node (ref "TET20") (pin "3") (pinfunction "3_3") (pintype "bidirectional"))
    )
    (net (code "91") (name "Net-(AIN_S0T-19-PadP19)") (class "Default")
      (node (ref "AIN_S0T") (pin "19") (pinfunction "19_19") (pintype "bidirectional"))
      (node (ref "AIN_S0T") (pin "P19") (pinfunction "19_P19") (pintype "bidirectional"))
      (node (ref "TET20") (pin "2") (pinfunction "2_2") (pintype "bidirectional"))
    )
    (net (code "92") (name "Net-(AIN_S0T-20-PadP20)") (class "Default")
      (node (ref "AIN_S0T") (pin "20") (pinfunction "20_20") (pintype "bidirectional"))
      (node (ref "AIN_S0T") (pin "P20") (pinfunction "20_P20") (pintype "bidirectional"))
      (node (ref "TET20") (pin "1") (pinfunction "1_1") (pintype "bidirectional"))
    )
    (net (code "93") (name "Net-(AIN_S0T-21-PadP21)") (class "Default")
      (node (ref "AIN_S0T") (pin "21") (pinfunction "21_21") (pintype "bidirectional"))
      (node (ref "AIN_S0T") (pin "P21") (pinfunction "21_P21") (pintype "bidirectional"))
      (node (ref "TET20") (pin "0") (pinfunction "0_0") (pintype "bidirectional"))
    )
    (net (code "94") (name "Net-(AIN_S0T-22-PadP22)") (class "Default")
      (node (ref "AIN_S0T") (pin "22") (pinfunction "22_22") (pintype "bidirectional"))
      (node (ref "AIN_S0T") (pin "P22") (pinfunction "22_P22") (pintype "bidirectional"))
      (node (ref "TET21") (pin "3") (pinfunction "3_3") (pintype "bidirectional"))
    )
    (net (code "95") (name "Net-(AIN_S0T-23-PadP23)") (class "Default")
      (node (ref "AIN_S0T") (pin "23") (pinfunction "23_23") (pintype "bidirectional"))
      (node (ref "AIN_S0T") (pin "P23") (pinfunction "23_P23") (pintype "bidirectional"))
      (node (ref "TET21") (pin "2") (pinfunction "2_2") (pintype "bidirectional"))
    )
    (net (code "96") (name "Net-(AIN_S0T-24-PadP24)") (class "Default")
      (node (ref "AIN_S0T") (pin "24") (pinfunction "24_24") (pintype "bidirectional"))
      (node (ref "AIN_S0T") (pin "P24") (pinfunction "24_P24") (pintype "bidirectional"))
      (node (ref "TET21") (pin "1") (pinfunction "1_1") (pintype "bidirectional"))
    )
    (net (code "97") (name "Net-(AIN_S0T-25-PadP25)") (class "Default")
      (node (ref "AIN_S0T") (pin "25") (pinfunction "25_25") (pintype "bidirectional"))
      (node (ref "AIN_S0T") (pin "P25") (pinfunction "25_P25") (pintype "bidirectional"))
      (node (ref "TET21") (pin "0") (pinfunction "0_0") (pintype "bidirectional"))
    )
    (net (code "98") (name "Net-(AIN_S0T-26-PadP26)") (class "Default")
      (node (ref "AIN_S0T") (pin "26") (pinfunction "26_26") (pintype "bidirectional"))
      (node (ref "AIN_S0T") (pin "P26") (pinfunction "26_P26") (pintype "bidirectional"))
      (node (ref "TET22") (pin "3") (pinfunction "3_3") (pintype "bidirectional"))
    )
    (net (code "99") (name "Net-(AIN_S0T-27-PadP27)") (class "Default")
      (node (ref "AIN_S0T") (pin "27") (pinfunction "27_27") (pintype "bidirectional"))
      (node (ref "AIN_S0T") (pin "P27") (pinfunction "27_P27") (pintype "bidirectional"))
      (node (ref "TET22") (pin "2") (pinfunction "2_2") (pintype "bidirectional"))
    )
    (net (code "100") (name "Net-(AIN_S0T-28-PadP28)") (class "Default")
      (node (ref "AIN_S0T") (pin "28") (pinfunction "28_28") (pintype "bidirectional"))
      (node (ref "AIN_S0T") (pin "P28") (pinfunction "28_P28") (pintype "bidirectional"))
      (node (ref "TET22") (pin "1") (pinfunction "1_1") (pintype "bidirectional"))
    )
    (net (code "101") (name "Net-(AIN_S0T-29-PadP29)") (class "Default")
      (node (ref "AIN_S0T") (pin "29") (pinfunction "29_29") (pintype "bidirectional"))
      (node (ref "AIN_S0T") (pin "P29") (pinfunction "29_P29") (pintype "bidirectional"))
      (node (ref "TET22") (pin "0") (pinfunction "0_0") (pintype "bidirectional"))
    )
    (net (code "102") (name "Net-(AIN_S0T-30-PadP30)") (class "Default")
      (node (ref "AIN_S0T") (pin "30") (pinfunction "30_30") (pintype "bidirectional"))
      (node (ref "AIN_S0T") (pin "P30") (pinfunction "30_P30") (pintype "bidirectional"))
      (node (ref "TET23") (pin "3") (pinfunction "3_3") (pintype "bidirectional"))
    )
    (net (code "103") (name "Net-(AIN_S0T-31-PadP31)") (class "Default")
      (node (ref "AIN_S0T") (pin "31") (pinfunction "31_31") (pintype "bidirectional"))
      (node (ref "AIN_S0T") (pin "P31") (pinfunction "31_P31") (pintype "bidirectional"))
      (node (ref "TET23") (pin "2") (pinfunction "2_2") (pintype "bidirectional"))
    )
    (net (code "104") (name "Net-(AIN_S0T-37-PadP37)") (class "Default")
      (node (ref "AIN_S0T") (pin "37") (pinfunction "37_37") (pintype "bidirectional"))
      (node (ref "AIN_S0T") (pin "P37") (pinfunction "37_P37") (pintype "bidirectional"))
      (node (ref "TET24") (pin "3") (pinfunction "3_3") (pintype "bidirectional"))
    )
    (net (code "105") (name "Net-(AIN_S0T-38-PadP38)") (class "Default")
      (node (ref "AIN_S0T") (pin "38") (pinfunction "38_38") (pintype "bidirectional"))
      (node (ref "AIN_S0T") (pin "P38") (pinfunction "38_P38") (pintype "bidirectional"))
      (node (ref "TET24") (pin "2") (pinfunction "2_2") (pintype "bidirectional"))
    )
    (net (code "106") (name "Net-(AIN_S0T-39-PadP39)") (class "Default")
      (node (ref "AIN_S0T") (pin "39") (pinfunction "39_39") (pintype "bidirectional"))
      (node (ref "AIN_S0T") (pin "P39") (pinfunction "39_P39") (pintype "bidirectional"))
      (node (ref "TET24") (pin "1") (pinfunction "1_1") (pintype "bidirectional"))
    )
    (net (code "107") (name "Net-(AIN_S0T-40-PadP40)") (class "Default")
      (node (ref "AIN_S0T") (pin "40") (pinfunction "40_40") (pintype "bidirectional"))
      (node (ref "AIN_S0T") (pin "P40") (pinfunction "40_P40") (pintype "bidirectional"))
      (node (ref "TET24") (pin "0") (pinfunction "0_0") (pintype "bidirectional"))
    )
    (net (code "108") (name "Net-(AIN_S0T-41-PadP41)") (class "Default")
      (node (ref "AIN_S0T") (pin "41") (pinfunction "41_41") (pintype "bidirectional"))
      (node (ref "AIN_S0T") (pin "P41") (pinfunction "41_P41") (pintype "bidirectional"))
      (node (ref "TET25") (pin "3") (pinfunction "3_3") (pintype "bidirectional"))
    )
    (net (code "109") (name "Net-(AIN_S0T-42-PadP42)") (class "Default")
      (node (ref "AIN_S0T") (pin "42") (pinfunction "42_42") (pintype "bidirectional"))
      (node (ref "AIN_S0T") (pin "P42") (pinfunction "42_P42") (pintype "bidirectional"))
      (node (ref "TET25") (pin "2") (pinfunction "2_2") (pintype "bidirectional"))
    )
    (net (code "110") (name "Net-(AIN_S0T-43-PadP43)") (class "Default")
      (node (ref "AIN_S0T") (pin "43") (pinfunction "43_43") (pintype "bidirectional"))
      (node (ref "AIN_S0T") (pin "P43") (pinfunction "43_P43") (pintype "bidirectional"))
      (node (ref "TET25") (pin "1") (pinfunction "1_1") (pintype "bidirectional"))
    )
    (net (code "111") (name "Net-(AIN_S0T-44-PadP44)") (class "Default")
      (node (ref "AIN_S0T") (pin "44") (pinfunction "44_44") (pintype "bidirectional"))
      (node (ref "AIN_S0T") (pin "P44") (pinfunction "44_P44") (pintype "bidirectional"))
      (node (ref "TET25") (pin "0") (pinfunction "0_0") (pintype "bidirectional"))
    )
    (net (code "112") (name "Net-(AIN_S0T-45-PadP45)") (class "Default")
      (node (ref "AIN_S0T") (pin "45") (pinfunction "45_45") (pintype "bidirectional"))
      (node (ref "AIN_S0T") (pin "P45") (pinfunction "45_P45") (pintype "bidirectional"))
      (node (ref "TET26") (pin "3") (pinfunction "3_3") (pintype "bidirectional"))
    )
    (net (code "113") (name "Net-(AIN_S0T-46-PadP46)") (class "Default")
      (node (ref "AIN_S0T") (pin "46") (pinfunction "46_46") (pintype "bidirectional"))
      (node (ref "AIN_S0T") (pin "P46") (pinfunction "46_P46") (pintype "bidirectional"))
      (node (ref "TET26") (pin "2") (pinfunction "2_2") (pintype "bidirectional"))
    )
    (net (code "114") (name "Net-(AIN_S0T-47-PadP47)") (class "Default")
      (node (ref "AIN_S0T") (pin "47") (pinfunction "47_47") (pintype "bidirectional"))
      (node (ref "AIN_S0T") (pin "P47") (pinfunction "47_P47") (pintype "bidirectional"))
      (node (ref "TET26") (pin "1") (pinfunction "1_1") (pintype "bidirectional"))
    )
    (net (code "115") (name "Net-(AIN_S0T-48-PadP48)") (class "Default")
      (node (ref "AIN_S0T") (pin "48") (pinfunction "48_48") (pintype "bidirectional"))
      (node (ref "AIN_S0T") (pin "P48") (pinfunction "48_P48") (pintype "bidirectional"))
      (node (ref "TET26") (pin "0") (pinfunction "0_0") (pintype "bidirectional"))
    )
    (net (code "116") (name "Net-(AIN_S0T-49-PadP49)") (class "Default")
      (node (ref "AIN_S0T") (pin "49") (pinfunction "49_49") (pintype "bidirectional"))
      (node (ref "AIN_S0T") (pin "P49") (pinfunction "49_P49") (pintype "bidirectional"))
      (node (ref "TET27") (pin "3") (pinfunction "3_3") (pintype "bidirectional"))
    )
    (net (code "117") (name "Net-(AIN_S0T-50-PadP50)") (class "Default")
      (node (ref "AIN_S0T") (pin "50") (pinfunction "50_50") (pintype "bidirectional"))
      (node (ref "AIN_S0T") (pin "P50") (pinfunction "50_P50") (pintype "bidirectional"))
      (node (ref "TET27") (pin "2") (pinfunction "2_2") (pintype "bidirectional"))
    )
    (net (code "118") (name "Net-(AIN_S0T-51-PadP51)") (class "Default")
      (node (ref "AIN_S0T") (pin "51") (pinfunction "51_51") (pintype "bidirectional"))
      (node (ref "AIN_S0T") (pin "P51") (pinfunction "51_P51") (pintype "bidirectional"))
      (node (ref "TET27") (pin "1") (pinfunction "1_1") (pintype "bidirectional"))
    )
    (net (code "119") (name "Net-(AIN_S0T-52-PadP52)") (class "Default")
      (node (ref "AIN_S0T") (pin "52") (pinfunction "52_52") (pintype "bidirectional"))
      (node (ref "AIN_S0T") (pin "P52") (pinfunction "52_P52") (pintype "bidirectional"))
      (node (ref "TET27") (pin "0") (pinfunction "0_0") (pintype "bidirectional"))
    )
    (net (code "120") (name "Net-(AIN_S0T-53-PadP53)") (class "Default")
      (node (ref "AIN_S0T") (pin "53") (pinfunction "53_53") (pintype "bidirectional"))
      (node (ref "AIN_S0T") (pin "P53") (pinfunction "53_P53") (pintype "bidirectional"))
      (node (ref "TET28") (pin "3") (pinfunction "3_3") (pintype "bidirectional"))
    )
    (net (code "121") (name "Net-(AIN_S0T-54-PadP54)") (class "Default")
      (node (ref "AIN_S0T") (pin "54") (pinfunction "54_54") (pintype "bidirectional"))
      (node (ref "AIN_S0T") (pin "P54") (pinfunction "54_P54") (pintype "bidirectional"))
      (node (ref "TET28") (pin "2") (pinfunction "2_2") (pintype "bidirectional"))
    )
    (net (code "122") (name "Net-(AIN_S0T-55-PadP55)") (class "Default")
      (node (ref "AIN_S0T") (pin "55") (pinfunction "55_55") (pintype "bidirectional"))
      (node (ref "AIN_S0T") (pin "P55") (pinfunction "55_P55") (pintype "bidirectional"))
      (node (ref "TET28") (pin "1") (pinfunction "1_1") (pintype "bidirectional"))
    )
    (net (code "123") (name "Net-(AIN_S0T-56-PadP56)") (class "Default")
      (node (ref "AIN_S0T") (pin "56") (pinfunction "56_56") (pintype "bidirectional"))
      (node (ref "AIN_S0T") (pin "P56") (pinfunction "56_P56") (pintype "bidirectional"))
      (node (ref "TET28") (pin "0") (pinfunction "0_0") (pintype "bidirectional"))
    )
    (net (code "124") (name "Net-(AIN_S0T-57-PadP57)") (class "Default")
      (node (ref "AIN_S0T") (pin "57") (pinfunction "57_57") (pintype "bidirectional"))
      (node (ref "AIN_S0T") (pin "P57") (pinfunction "57_P57") (pintype "bidirectional"))
      (node (ref "TET29") (pin "3") (pinfunction "3_3") (pintype "bidirectional"))
    )
    (net (code "125") (name "Net-(AIN_S0T-58-PadP58)") (class "Default")
      (node (ref "AIN_S0T") (pin "58") (pinfunction "58_58") (pintype "bidirectional"))
      (node (ref "AIN_S0T") (pin "P58") (pinfunction "58_P58") (pintype "bidirectional"))
      (node (ref "TET29") (pin "2") (pinfunction "2_2") (pintype "bidirectional"))
    )
    (net (code "126") (name "Net-(AIN_S0T-59-PadP59)") (class "Default")
      (node (ref "AIN_S0T") (pin "59") (pinfunction "59_59") (pintype "bidirectional"))
      (node (ref "AIN_S0T") (pin "P59") (pinfunction "59_P59") (pintype "bidirectional"))
      (node (ref "TET29") (pin "1") (pinfunction "1_1") (pintype "bidirectional"))
    )
    (net (code "127") (name "Net-(AIN_S0T-60-PadP60)") (class "Default")
      (node (ref "AIN_S0T") (pin "60") (pinfunction "60_60") (pintype "bidirectional"))
      (node (ref "AIN_S0T") (pin "P60") (pinfunction "60_P60") (pintype "bidirectional"))
      (node (ref "TET29") (pin "0") (pinfunction "0_0") (pintype "bidirectional"))
    )
    (net (code "128") (name "Net-(AIN_S0T-61-PadP61)") (class "Default")
      (node (ref "AIN_S0T") (pin "61") (pinfunction "61_61") (pintype "bidirectional"))
      (node (ref "AIN_S0T") (pin "P61") (pinfunction "61_P61") (pintype "bidirectional"))
      (node (ref "TET30") (pin "3") (pinfunction "3_3") (pintype "bidirectional"))
    )
    (net (code "129") (name "Net-(AIN_S0T-62-PadP62)") (class "Default")
      (node (ref "AIN_S0T") (pin "62") (pinfunction "62_62") (pintype "bidirectional"))
      (node (ref "AIN_S0T") (pin "P62") (pinfunction "62_P62") (pintype "bidirectional"))
      (node (ref "TET30") (pin "2") (pinfunction "2_2") (pintype "bidirectional"))
    )
    (net (code "130") (name "Net-(AIN_S0T-63-PadP63)") (class "Default")
      (node (ref "AIN_S0T") (pin "63") (pinfunction "63_63") (pintype "bidirectional"))
      (node (ref "AIN_S0T") (pin "P63") (pinfunction "63_P63") (pintype "bidirectional"))
      (node (ref "TET30") (pin "1") (pinfunction "1_1") (pintype "bidirectional"))
    )
    (net (code "131") (name "Net-(AIN_S0T-64-PadP64)") (class "Default")
      (node (ref "AIN_S0T") (pin "64") (pinfunction "64_64") (pintype "bidirectional"))
      (node (ref "AIN_S0T") (pin "P64") (pinfunction "64_P64") (pintype "bidirectional"))
      (node (ref "TET30") (pin "0") (pinfunction "0_0") (pintype "bidirectional"))
    )
    (net (code "132") (name "Net-(AIN_S0T-Pad32)") (class "Default")
      (node (ref "AIN_S0T") (pin "32") (pinfunction "32_32") (pintype "bidirectional"))
      (node (ref "TET23") (pin "1") (pinfunction "1_1") (pintype "bidirectional"))
    )
    (net (code "133") (name "Net-(AIN_S0T-Pad33)") (class "Default")
      (node (ref "AIN_S0T") (pin "33") (pinfunction "33_33") (pintype "bidirectional"))
      (node (ref "TET23") (pin "0") (pinfunction "0_0") (pintype "bidirectional"))
    )
    (net (code "134") (name "Net-(AIN_S0T-Pad65)") (class "Default")
      (node (ref "AIN_S0T") (pin "65") (pinfunction "65_65") (pintype "bidirectional"))
      (node (ref "TET31") (pin "3") (pinfunction "3_3") (pintype "bidirectional"))
    )
    (net (code "135") (name "Net-(AIN_S0T-Pad66)") (class "Default")
      (node (ref "AIN_S0T") (pin "66") (pinfunction "66_66") (pintype "bidirectional"))
      (node (ref "TET31") (pin "2") (pinfunction "2_2") (pintype "bidirectional"))
    )
    (net (code "136") (name "Net-(AIN_S0T-Pad67)") (class "Default")
      (node (ref "AIN_S0T") (pin "67") (pinfunction "67_67") (pintype "bidirectional"))
      (node (ref "TET31") (pin "1") (pinfunction "1_1") (pintype "bidirectional"))
    )
    (net (code "137") (name "Net-(AIN_S0T-Pad68)") (class "Default")
      (node (ref "AIN_S0T") (pin "68") (pinfunction "68_68") (pintype "bidirectional"))
      (node (ref "TET31") (pin "0") (pinfunction "0_0") (pintype "bidirectional"))
    )
    (net (code "138") (name "Net-(SHLD_A0-0)") (class "Default")
      (node (ref "SHLD_A0") (pin "P$1") (pinfunction "0_P$1") (pintype "bidirectional"))
      (node (ref "SJ_A0") (pin "COM") (pinfunction "COM_COM") (pintype "passive"))
    )
    (net (code "139") (name "Net-(SHLD_A1-0)") (class "Default")
      (node (ref "SHLD_A1") (pin "P$1") (pinfunction "0_P$1") (pintype "bidirectional"))
      (node (ref "SJ_A1") (pin "COM") (pinfunction "COM_COM") (pintype "passive"))
    )
    (net (code "140") (name "Net-(SHLD_B0-0)") (class "Default")
      (node (ref "SHLD_B0") (pin "P$1") (pinfunction "0_P$1") (pintype "bidirectional"))
      (node (ref "SJ_B0") (pin "COM") (pinfunction "COM_COM") (pintype "passive"))
    )
    (net (code "141") (name "Net-(SHLD_B1-0)") (class "Default")
      (node (ref "SHLD_B1") (pin "P$1") (pinfunction "0_P$1") (pintype "bidirectional"))
      (node (ref "SJ_B1") (pin "COM") (pinfunction "COM_COM") (pintype "passive"))
    )
  )
)
